# bondibarWirelessDongle.net
KiCad netlist of a schematic drawn in EAGLE
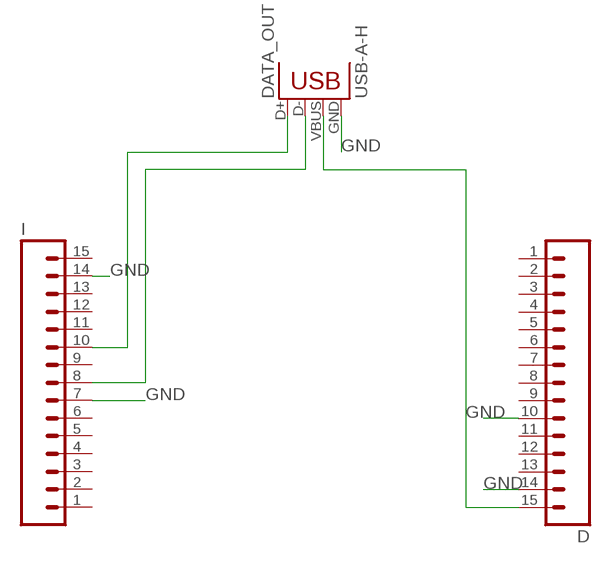
[diagram p0: schematic, sheet 1]

(export (version "E")
  (design (tool "Eeschema 10.0.6"))
  (components
    (comp (ref "D")
      (value "M15")
      (footprint "eagle-import:1X15")
      (libsource (lib "eagle-import") (part "M15"))
    )
    (comp (ref "DATA_OUT")
      (value "USB-A-H")
      (footprint "eagle-import:USB-A-H")
      (libsource (lib "eagle-import") (part "USB-A-H"))
    )
    (comp (ref "I")
      (value "M15")
      (footprint "eagle-import:1X15")
      (libsource (lib "eagle-import") (part "M15"))
    )
  )
  (nets
    (net (code "1") (name "/GND") (class "Default")
      (node (ref "D") (pin "10") (pinfunction "10_10") (pintype "passive"))
      (node (ref "D") (pin "14") (pinfunction "14_14") (pintype "passive"))
      (node (ref "DATA_OUT") (pin "GND") (pinfunction "GND_GND") (pintype "bidirectional"))
      (node (ref "I") (pin "14") (pinfunction "14_14") (pintype "passive"))
      (node (ref "I") (pin "7") (pinfunction "7_7") (pintype "passive"))
    )
    (net (code "2") (name "Net-(D-Pad15)") (class "Default")
      (node (ref "D") (pin "15") (pinfunction "15_15") (pintype "passive"))
      (node (ref "DATA_OUT") (pin "VBUS") (pinfunction "VBUS_VBUS") (pintype "bidirectional"))
    )
    (net (code "3") (name "Net-(DATA_OUT-PadD+)") (class "Default")
      (node (ref "DATA_OUT") (pin "D+") (pinfunction "D+_D+") (pintype "bidirectional"))
      (node (ref "I") (pin "10") (pinfunction "10_10") (pintype "passive"))
    )
    (net (code "4") (name "Net-(DATA_OUT-PadD-)") (class "Default")
      (node (ref "DATA_OUT") (pin "D-") (pinfunction "D-_D-") (pintype "bidirectional"))
      (node (ref "I") (pin "8") (pinfunction "8_8") (pintype "passive"))
    )
    (net (code "5") (name "unconnected-(D-Pad1)") (class "Default")
      (node (ref "D") (pin "1") (pinfunction "1_1") (pintype "passive"))
    )
    (net (code "6") (name "unconnected-(D-Pad2)") (class "Default")
      (node (ref "D") (pin "2") (pinfunction "2_2") (pintype "passive"))
    )
    (net (code "7") (name "unconnected-(D-Pad3)") (class "Default")
      (node (ref "D") (pin "3") (pinfunction "3_3") (pintype "passive"))
    )
    (net (code "8") (name "unconnected-(D-Pad4)") (class "Default")
      (node (ref "D") (pin "4") (pinfunction "4_4") (pintype "passive"))
    )
    (net (code "9") (name "unconnected-(D-Pad5)") (class "Default")
      (node (ref "D") (pin "5") (pinfunction "5_5") (pintype "passive"))
    )
    (net (code "10") (name "unconnected-(D-Pad6)") (class "Default")
      (node (ref "D") (pin "6") (pinfunction "6_6") (pintype "passive"))
    )
    (net (code "11") (name "unconnected-(D-Pad7)") (class "Default")
      (node (ref "D") (pin "7") (pinfunction "7_7") (pintype "passive"))
    )
    (net (code "12") (name "unconnected-(D-Pad8)") (class "Default")
      (node (ref "D") (pin "8") (pinfunction "8_8") (pintype "passive"))
    )
    (net (code "13") (name "unconnected-(D-Pad9)") (class "Default")
      (node (ref "D") (pin "9") (pinfunction "9_9") (pintype "passive"))
    )
    (net (code "14") (name "unconnected-(D-Pad11)") (class "Default")
      (node (ref "D") (pin "11") (pinfunction "11_11") (pintype "passive"))
    )
    (net (code "15") (name "unconnected-(D-Pad12)") (class "Default")
      (node (ref "D") (pin "12") (pinfunction "12_12") (pintype "passive"))
    )
    (net (code "16") (name "unconnected-(D-Pad13)") (class "Default")
      (node (ref "D") (pin "13") (pinfunction "13_13") (pintype "passive"))
    )
    (net (code "17") (name "unconnected-(I-Pad1)") (class "Default")
      (node (ref "I") (pin "1") (pinfunction "1_1") (pintype "passive"))
    )
    (net (code "18") (name "unconnected-(I-Pad2)") (class "Default")
      (node (ref "I") (pin "2") (pinfunction "2_2") (pintype "passive"))
    )
    (net (code "19") (name "unconnected-(I-Pad3)") (class "Default")
      (node (ref "I") (pin "3") (pinfunction "3_3") (pintype "passive"))
    )
    (net (code "20") (name "unconnected-(I-Pad4)") (class "Default")
      (node (ref "I") (pin "4") (pinfunction "4_4") (pintype "passive"))
    )
    (net (code "21") (name "unconnected-(I-Pad5)") (class "Default")
      (node (ref "I") (pin "5") (pinfunction "5_5") (pintype "passive"))
    )
    (net (code "22") (name "unconnected-(I-Pad6)") (class "Default")
      (node (ref "I") (pin "6") (pinfunction "6_6") (pintype "passive"))
    )
    (net (code "23") (name "unconnected-(I-Pad9)") (class "Default")
      (node (ref "I") (pin "9") (pinfunction "9_9") (pintype "passive"))
    )
    (net (code "24") (name "unconnected-(I-Pad11)") (class "Default")
      (node (ref "I") (pin "11") (pinfunction "11_11") (pintype "passive"))
    )
    (net (code "25") (name "unconnected-(I-Pad12)") (class "Default")
      (node (ref "I") (pin "12") (pinfunction "12_12") (pintype "passive"))
    )
    (net (code "26") (name "unconnected-(I-Pad13)") (class "Default")
      (node (ref "I") (pin "13") (pinfunction "13_13") (pintype "passive"))
    )
    (net (code "27") (name "unconnected-(I-Pad15)") (class "Default")
      (node (ref "I") (pin "15") (pinfunction "15_15") (pintype "passive"))
    )
  )
)
